# Sheet1.net
KiCad netlist of a schematic drawn in Altium Designer
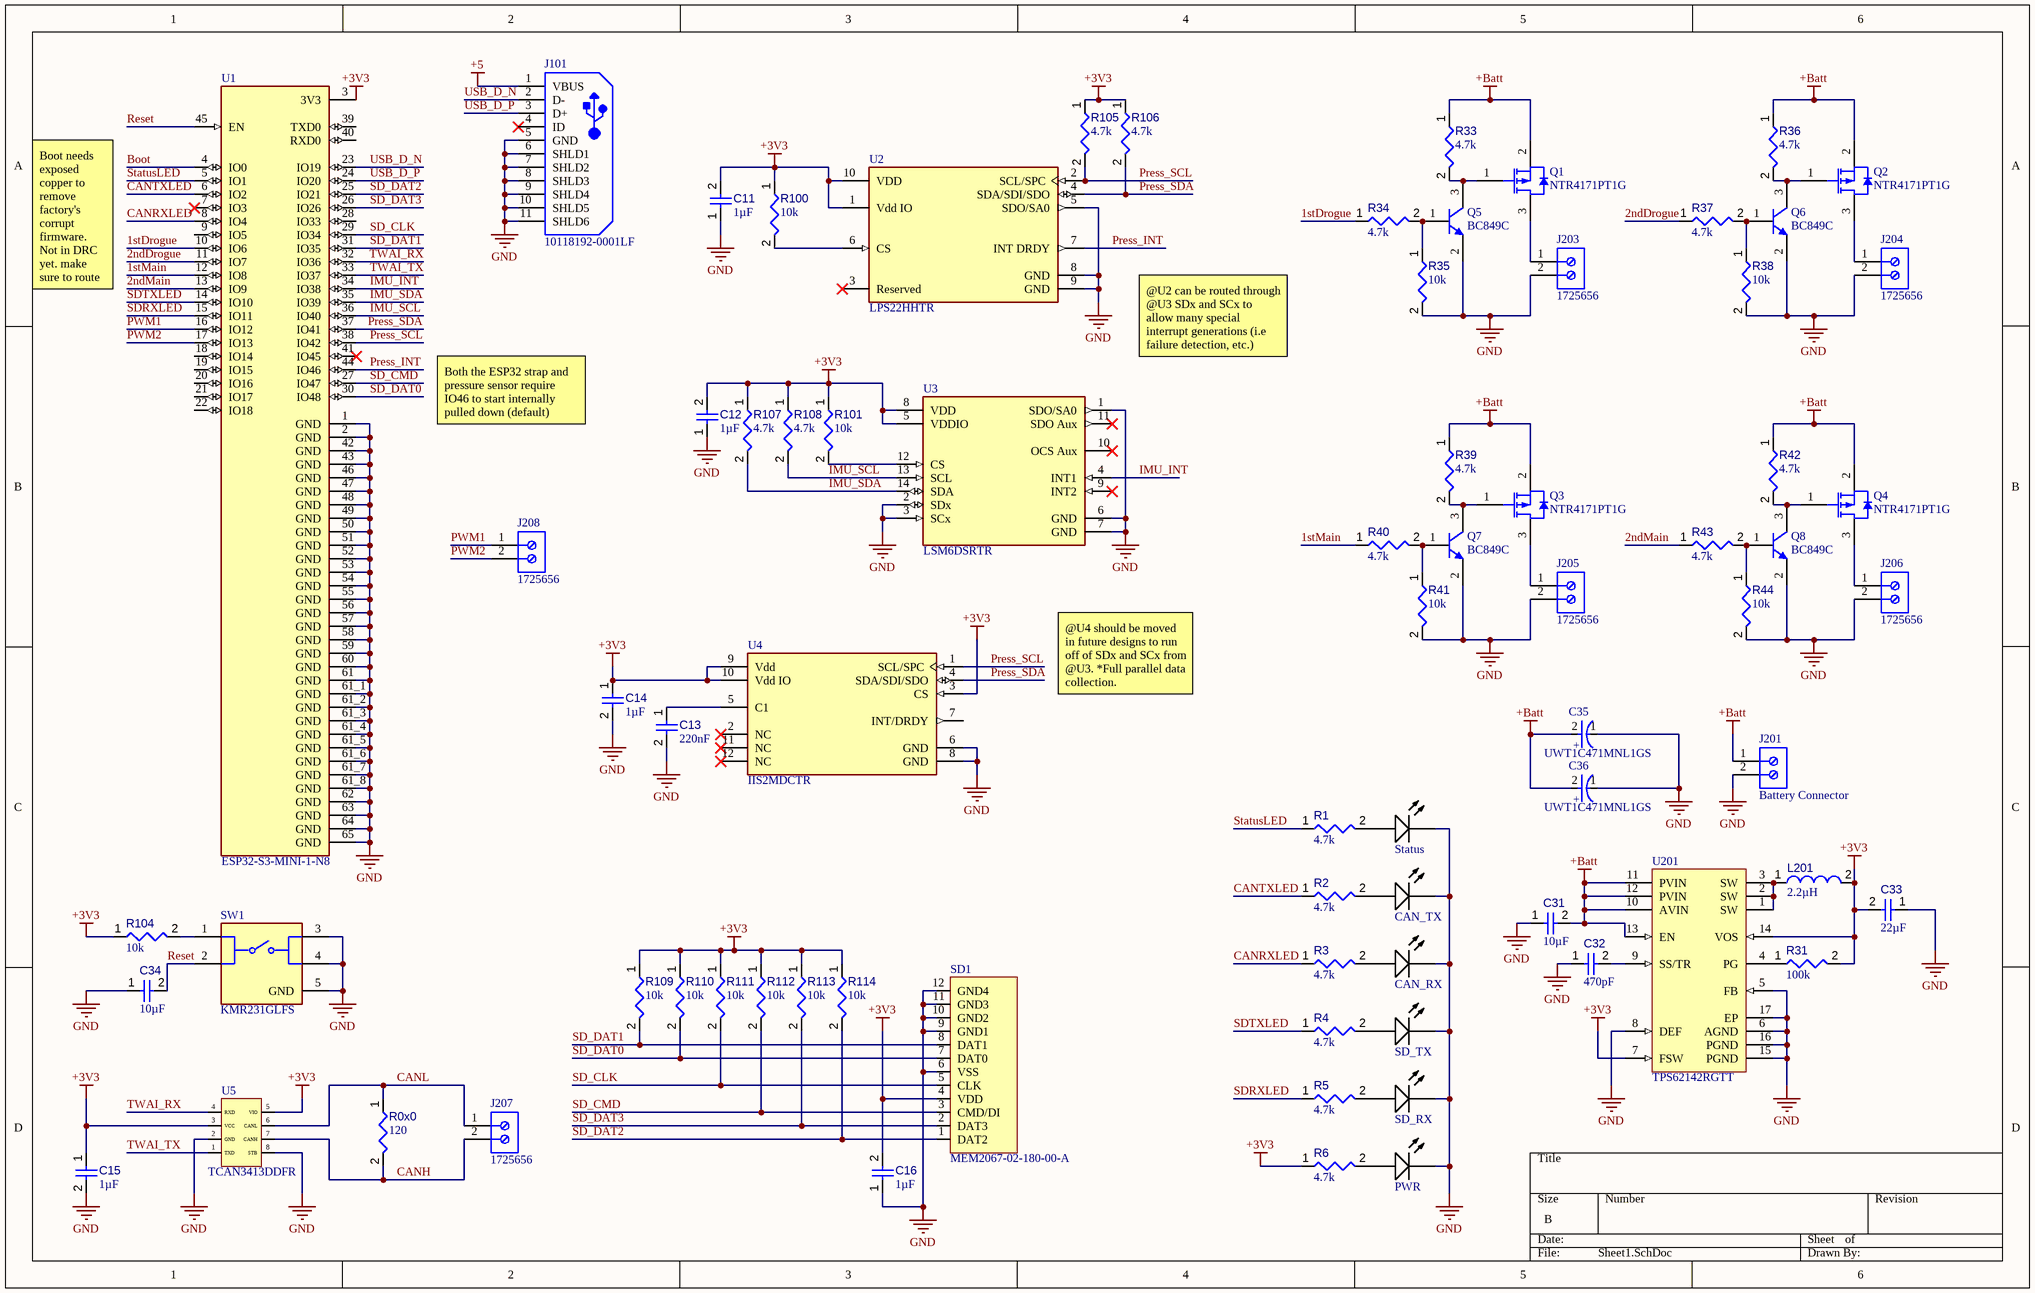
[diagram p0: Sheet1.SchDoc]

(export (version "E")
  (design (tool "Eeschema 10.0.6"))
  (components
    (comp (ref "C11")
      (value "1µF")
      (footprint "CAPC1005X55X25LL05T10")
      (description "Chip Capacitor, 1 uF, +/- 10%, 6.3 V, 0402 (1005 Metric)")
      (fields (field (name "TOLERANCE") "10%") (field (name "Comment") "Capacitor 1 uF +/- 10% 6.3 V 0402"))
      (libsource (lib "UTD") (part "CAP-NP-2"))
    )
    (comp (ref "C12")
      (value "1µF")
      (footprint "CAPC1005X55X25LL05T10")
      (description "Chip Capacitor, 1 uF, +/- 10%, 6.3 V, 0402 (1005 Metric)")
      (fields (field (name "TOLERANCE") "10%") (field (name "Comment") "Capacitor 1 uF +/- 10% 6.3 V 0402"))
      (libsource (lib "UTD") (part "CAP-NP-2"))
    )
    (comp (ref "C13")
      (value "220nF")
      (footprint "CAPC0402(1005)60_L")
      (description "Chip Capacitor, 220nF +/-20%, 10V, 0402, Thickness 0.6 mm")
      (fields (field (name "TOLERANCE") "10%") (field (name "Comment") "Capacitor 220nF +/-20% 10V 0402"))
      (libsource (lib "UTD") (part "CAP-NP-2"))
    )
    (comp (ref "C14")
      (value "1µF")
      (footprint "CAPC1005X55X25LL05T10")
      (description "Chip Capacitor, 1 uF, +/- 10%, 6.3 V, 0402 (1005 Metric)")
      (fields (field (name "TOLERANCE") "10%") (field (name "Comment") "Capacitor 1 uF +/- 10% 6.3 V 0402"))
      (libsource (lib "UTD") (part "CAP-NP-2"))
    )
    (comp (ref "C15")
      (value "1µF")
      (footprint "CAPC1005X55X25LL05T10")
      (description "Chip Capacitor, 1 uF, +/- 10%, 6.3 V, 0402 (1005 Metric)")
      (fields (field (name "TOLERANCE") "10%") (field (name "Comment") "Capacitor 1 uF +/- 10% 6.3 V 0402"))
      (libsource (lib "UTD") (part "CAP-NP-2"))
    )
    (comp (ref "C16")
      (value "1µF")
      (footprint "CAPC1005X55X25LL05T10")
      (description "Chip Capacitor, 1 uF, +/- 10%, 6.3 V, 0402 (1005 Metric)")
      (fields (field (name "TOLERANCE") "10%") (field (name "Comment") "Capacitor 1 uF +/- 10% 6.3 V 0402"))
      (libsource (lib "UTD") (part "CAP-NP-2"))
    )
    (comp (ref "C31")
      (value "10µF")
      (footprint "CAPC0603(1608)100_L")
      (description "Chip Capacitor, 10µF +/-20%, 10V, 0603, Thickness 1 mm")
      (fields (field (name "TOLERANCE") "10%") (field (name "Comment") "Capacitor 10µF +/-20% 10V 0603"))
      (libsource (lib "UTD") (part "CAP-NP-2"))
    )
    (comp (ref "C32")
      (value "470pF")
      (footprint "CAPC0603(1608)100_L")
      (description "Chip Capacitor, 470pF +/-20%, 10V, 0603, Thickness 1 mm")
      (fields (field (name "TOLERANCE") "10%") (field (name "Comment") "Capacitor 470pF +/-20% 50V 0402"))
      (libsource (lib "UTD") (part "CAP-NP-2"))
    )
    (comp (ref "C33")
      (value "22µF")
      (footprint "CAPC0603(1608)100_L")
      (description "Chip Capacitor, 10µF +/-20%, 10V, 0603, Thickness 1 mm")
      (fields (field (name "TOLERANCE") "10%") (field (name "Comment") "Capacitor 10µF +/-20% 10V 0603"))
      (libsource (lib "UTD") (part "CAP-NP-2"))
    )
    (comp (ref "C34")
      (value "10µF")
      (footprint "CAPC0603(1608)100_L")
      (description "Chip Capacitor, 10µF +/-20%, 10V, 0603, Thickness 1 mm")
      (fields (field (name "TOLERANCE") "10%") (field (name "Comment") "Capacitor 10µF +/-20% 10V 0603"))
      (libsource (lib "The University of Texas at Dallas") (part "CAP-NP-2"))
    )
    (comp (ref "C35")
      (value "UWT1C471MNL1GS")
      (footprint "FP-UWT1C471MNL1GS-MFG")
      (description "CAP ALUM 470UF 20% 16V SMD")
      (fields (field (name "VOLTAGE") "16V") (field (name "TOLERANCE") "20%"))
      (libsource (lib "Altium Content Vault") (part "203bc49f2ac43e59fd269a8c329ed05"))
    )
    (comp (ref "C36")
      (value "UWT1C471MNL1GS")
      (footprint "FP-UWT1C471MNL1GS-MFG")
      (description "CAP ALUM 470UF 20% 16V SMD")
      (fields (field (name "VOLTAGE") "16V") (field (name "TOLERANCE") "20%"))
      (libsource (lib "Altium Content Vault") (part "203bc49f2ac43e59fd269a8c329ed05"))
    )
    (comp (ref "CAN_RX")
      (value "HSMW-C191")
      (footprint "AVAG-HSMW-C191_V")
      (description "LED Uni-Color White, 78 mW, 20 mA, -40 to 85 degC, 2-Pin SMD, RoHS, Tape and Reel")
      (fields (field (name "POWER") "78mW") (field (name "MANUFACTURER") "Avago"))
      (libsource (lib "UTD") (part "LED-WHITE-AK-2"))
    )
    (comp (ref "CAN_TX")
      (value "HSMW-C191")
      (footprint "AVAG-HSMW-C191_V")
      (description "LED Uni-Color White, 78 mW, 20 mA, -40 to 85 degC, 2-Pin SMD, RoHS, Tape and Reel")
      (fields (field (name "POWER") "78mW") (field (name "MANUFACTURER") "Avago"))
      (libsource (lib "UTD") (part "LED-WHITE-AK-2"))
    )
    (comp (ref "J101")
      (value "10118192-0001LF")
      (footprint "FCI-10118192-0001LF-5_V")
      (description "Micro USB B Type Receptacle, -55 to 85 degC, 5-Pin SMD, RoHS, Tape and Reel")
      (fields (field (name "MANUFACTURER") "FCI"))
      (libsource (lib "Altium Content Vault") (part "USB-5-6SHLD"))
    )
    (comp (ref "J201")
      (value "Battery Connector")
      (footprint "PHOE-1725656-2")
      (description "Male Header, Pitch 2.54 mm, 1 x 2 Position, Height 9 mm, Tail Length 3.5 mm")
      (fields
        (field (name "MANUFACTURER PART NO.") "1725656")
        (field (name "MANUFACTURER") "Phoenix Contact")
      )
      (libsource (lib "Altium Content Vault") (part "CN-1P-F-TB2"))
    )
    (comp (ref "J203")
      (value "1725656")
      (footprint "PHOE-1725656-2")
      (description "Male Header, Pitch 2.54 mm, 1 x 2 Position, Height 9 mm, Tail Length 3.5 mm")
      (fields (field (name "MANUFACTURER") "Phoenix Contact"))
      (libsource (lib "Altium Content Vault") (part "CN-1P-F-TB2"))
    )
    (comp (ref "J204")
      (value "1725656")
      (footprint "PHOE-1725656-2")
      (description "Male Header, Pitch 2.54 mm, 1 x 2 Position, Height 9 mm, Tail Length 3.5 mm")
      (fields (field (name "MANUFACTURER") "Phoenix Contact"))
      (libsource (lib "Altium Content Vault") (part "CN-1P-F-TB2"))
    )
    (comp (ref "J205")
      (value "1725656")
      (footprint "PHOE-1725656-2")
      (description "Male Header, Pitch 2.54 mm, 1 x 2 Position, Height 9 mm, Tail Length 3.5 mm")
      (fields (field (name "MANUFACTURER") "Phoenix Contact"))
      (libsource (lib "Altium Content Vault") (part "CN-1P-F-TB2"))
    )
    (comp (ref "J206")
      (value "1725656")
      (footprint "PHOE-1725656-2")
      (description "Male Header, Pitch 2.54 mm, 1 x 2 Position, Height 9 mm, Tail Length 3.5 mm")
      (fields (field (name "MANUFACTURER") "Phoenix Contact"))
      (libsource (lib "Altium Content Vault") (part "CN-1P-F-TB2"))
    )
    (comp (ref "J207")
      (value "1725656")
      (footprint "PHOE-1725656-2")
      (description "Male Header, Pitch 2.54 mm, 1 x 2 Position, Height 9 mm, Tail Length 3.5 mm")
      (fields (field (name "MANUFACTURER") "Phoenix Contact"))
      (libsource (lib "Altium Content Vault") (part "CN-1P-F-TB2"))
    )
    (comp (ref "J208")
      (value "1725656")
      (footprint "PHOE-1725656-2")
      (description "Male Header, Pitch 2.54 mm, 1 x 2 Position, Height 9 mm, Tail Length 3.5 mm")
      (fields (field (name "MANUFACTURER") "Phoenix Contact"))
      (libsource (lib "Altium Content Vault") (part "CN-1P-F-TB2"))
    )
    (comp (ref "L201")
      (value "2.2µH")
      (footprint "INDC2520X100X60NL20T20")
      (description "Chip Inductor, 2.2 uH, +/- 20%, -55 to 125 degC, 1008 (2520 Metric), RoHS, Tape and Reel")
      (fields (field (name "TOLERANCE") "20%") (field (name "MANUFACTURER") "Murata"))
      (libsource (lib "UTD") (part "IND-2"))
    )
    (comp (ref "PWR")
      (value "HSMW-C191")
      (footprint "AVAG-HSMW-C191_V")
      (description "LED Uni-Color White, 78 mW, 20 mA, -40 to 85 degC, 2-Pin SMD, RoHS, Tape and Reel")
      (fields (field (name "POWER") "78mW") (field (name "MANUFACTURER") "Avago"))
      (libsource (lib "UTD") (part "LED-WHITE-AK-2"))
    )
    (comp (ref "Q1")
      (value "NTR4171PT1G")
      (footprint "ONSC-SOT-23-3-318-08_V")
      (description "Power MOSFET, -30 V, 3.5 A, Single P-Channel, 3-Pin SOT-23, Pb-Free, Tape and Reel")
      (fields (field (name "MANUFACTURER") "On Semiconductor"))
      (libsource (lib "Altium Content Vault") (part "ONSC-PMOS-G1S2D3-3_D"))
    )
    (comp (ref "Q2")
      (value "NTR4171PT1G")
      (footprint "ONSC-SOT-23-3-318-08_V")
      (description "Power MOSFET, -30 V, 3.5 A, Single P-Channel, 3-Pin SOT-23, Pb-Free, Tape and Reel")
      (fields (field (name "MANUFACTURER") "On Semiconductor"))
      (libsource (lib "Altium Content Vault") (part "ONSC-PMOS-G1S2D3-3_D"))
    )
    (comp (ref "Q3")
      (value "NTR4171PT1G")
      (footprint "ONSC-SOT-23-3-318-08_V")
      (description "Power MOSFET, -30 V, 3.5 A, Single P-Channel, 3-Pin SOT-23, Pb-Free, Tape and Reel")
      (fields (field (name "MANUFACTURER") "On Semiconductor"))
      (libsource (lib "Altium Content Vault") (part "ONSC-PMOS-G1S2D3-3_D"))
    )
    (comp (ref "Q4")
      (value "NTR4171PT1G")
      (footprint "ONSC-SOT-23-3-318-08_V")
      (description "Power MOSFET, -30 V, 3.5 A, Single P-Channel, 3-Pin SOT-23, Pb-Free, Tape and Reel")
      (fields (field (name "MANUFACTURER") "On Semiconductor"))
      (libsource (lib "Altium Content Vault") (part "ONSC-PMOS-G1S2D3-3_D"))
    )
    (comp (ref "Q5")
      (value "BC849C")
      (footprint "INF-SOT23_L")
      (description "NPN Silicon AF Transistor, 30 V VCEO, 100 mA IC, SOT23, Reel, Green")
      (fields (field (name "MANUFACTURER") "Infineon"))
      (libsource (lib "Altium Content Vault") (part "INF-BJTNPN-BEC-3"))
    )
    (comp (ref "Q6")
      (value "BC849C")
      (footprint "INF-SOT23_L")
      (description "NPN Silicon AF Transistor, 30 V VCEO, 100 mA IC, SOT23, Reel, Green")
      (fields (field (name "MANUFACTURER") "Infineon"))
      (libsource (lib "Altium Content Vault") (part "INF-BJTNPN-BEC-3"))
    )
    (comp (ref "Q7")
      (value "BC849C")
      (footprint "INF-SOT23_L")
      (description "NPN Silicon AF Transistor, 30 V VCEO, 100 mA IC, SOT23, Reel, Green")
      (fields (field (name "MANUFACTURER") "Infineon"))
      (libsource (lib "Altium Content Vault") (part "INF-BJTNPN-BEC-3"))
    )
    (comp (ref "Q8")
      (value "BC849C")
      (footprint "INF-SOT23_L")
      (description "NPN Silicon AF Transistor, 30 V VCEO, 100 mA IC, SOT23, Reel, Green")
      (fields (field (name "MANUFACTURER") "Infineon"))
      (libsource (lib "Altium Content Vault") (part "INF-BJTNPN-BEC-3"))
    )
    (comp (ref "R0x0")
      (value "120")
      (footprint "RESC0603(1608)_L")
      (description "Chip Resistor, 120 Ohms, +/-5 %, 0.1 W, -55 to 155 degC, 0603")
      (fields (field (name "POWER") "100mW") (field (name "TOLERANCE") "5%"))
      (libsource (lib "The University of Texas at Dallas") (part "RES-2"))
    )
    (comp (ref "R1")
      (value "4.7k")
      (footprint "RESC1005X40X25ML05T05")
      (description "Chip Resistor, 4.7 KOhm, +/- 1%, 63 mW, -55 to 155 degC, 0402 (1005 Metric)")
      (fields (field (name "TOLERANCE") "1%") (field (name "POWER") "63mW"))
      (libsource (lib "UTD") (part "RES-2"))
    )
    (comp (ref "R2")
      (value "4.7k")
      (footprint "RESC1005X40X25ML05T05")
      (description "Chip Resistor, 4.7 KOhm, +/- 1%, 63 mW, -55 to 155 degC, 0402 (1005 Metric)")
      (fields (field (name "TOLERANCE") "1%") (field (name "POWER") "63mW"))
      (libsource (lib "UTD") (part "RES-2"))
    )
    (comp (ref "R3")
      (value "4.7k")
      (footprint "RESC1005X40X25ML05T05")
      (description "Chip Resistor, 4.7 KOhm, +/- 1%, 63 mW, -55 to 155 degC, 0402 (1005 Metric)")
      (fields (field (name "TOLERANCE") "1%") (field (name "POWER") "63mW"))
      (libsource (lib "UTD") (part "RES-2"))
    )
    (comp (ref "R4")
      (value "4.7k")
      (footprint "RESC1005X40X25ML05T05")
      (description "Chip Resistor, 4.7 KOhm, +/- 1%, 63 mW, -55 to 155 degC, 0402 (1005 Metric)")
      (fields (field (name "TOLERANCE") "1%") (field (name "POWER") "63mW"))
      (libsource (lib "UTD") (part "RES-2"))
    )
    (comp (ref "R5")
      (value "4.7k")
      (footprint "RESC1005X40X25ML05T05")
      (description "Chip Resistor, 4.7 KOhm, +/- 1%, 63 mW, -55 to 155 degC, 0402 (1005 Metric)")
      (fields (field (name "TOLERANCE") "1%") (field (name "POWER") "63mW"))
      (libsource (lib "UTD") (part "RES-2"))
    )
    (comp (ref "R6")
      (value "4.7k")
      (footprint "RESC1005X40X25ML05T05")
      (description "Chip Resistor, 4.7 KOhm, +/- 1%, 63 mW, -55 to 155 degC, 0402 (1005 Metric)")
      (fields (field (name "TOLERANCE") "1%") (field (name "POWER") "63mW"))
      (libsource (lib "UTD") (part "RES-2"))
    )
    (comp (ref "R31")
      (value "100k")
      (footprint "RESC0402(1005)_L")
      (description "Chip Resistor, 100 kOhms, +/-1 %, 63 mW, -55 to 155 degC, 0402")
      (fields (field (name "TOLERANCE") "1%") (field (name "POWER") "63mW"))
      (libsource (lib "UTD") (part "RES-2"))
    )
    (comp (ref "R33")
      (value "4.7k")
      (footprint "RESC1005X40X25ML05T05")
      (description "Chip Resistor, 4.7 KOhm, +/- 1%, 63 mW, -55 to 155 degC, 0402 (1005 Metric)")
      (fields (field (name "TOLERANCE") "1%") (field (name "POWER") "63mW"))
      (libsource (lib "UTD") (part "RES-2"))
    )
    (comp (ref "R34")
      (value "4.7k")
      (footprint "RESC1005X40X25ML05T05")
      (description "Chip Resistor, 4.7 KOhm, +/- 1%, 63 mW, -55 to 155 degC, 0402 (1005 Metric)")
      (fields (field (name "TOLERANCE") "1%") (field (name "POWER") "63mW"))
      (libsource (lib "UTD") (part "RES-2"))
    )
    (comp (ref "R35")
      (value "10k")
      (footprint "RESC1005X40X25ML05T05")
      (description "Chip Resistor, 10 KOhm, +/- 1%, 63 mW, -55 to 155 degC, 0402 (1005 Metric)")
      (fields (field (name "POWER") "63mW") (field (name "TOLERANCE") "1%"))
      (libsource (lib "UTD") (part "RES-2"))
    )
    (comp (ref "R36")
      (value "4.7k")
      (footprint "RESC1005X40X25ML05T05")
      (description "Chip Resistor, 4.7 KOhm, +/- 1%, 63 mW, -55 to 155 degC, 0402 (1005 Metric)")
      (fields (field (name "TOLERANCE") "1%") (field (name "POWER") "63mW"))
      (libsource (lib "UTD") (part "RES-2"))
    )
    (comp (ref "R37")
      (value "4.7k")
      (footprint "RESC1005X40X25ML05T05")
      (description "Chip Resistor, 4.7 KOhm, +/- 1%, 63 mW, -55 to 155 degC, 0402 (1005 Metric)")
      (fields (field (name "TOLERANCE") "1%") (field (name "POWER") "63mW"))
      (libsource (lib "UTD") (part "RES-2"))
    )
    (comp (ref "R38")
      (value "10k")
      (footprint "RESC1005X40X25ML05T05")
      (description "Chip Resistor, 10 KOhm, +/- 1%, 63 mW, -55 to 155 degC, 0402 (1005 Metric)")
      (fields (field (name "POWER") "63mW") (field (name "TOLERANCE") "1%"))
      (libsource (lib "UTD") (part "RES-2"))
    )
    (comp (ref "R39")
      (value "4.7k")
      (footprint "RESC1005X40X25ML05T05")
      (description "Chip Resistor, 4.7 KOhm, +/- 1%, 63 mW, -55 to 155 degC, 0402 (1005 Metric)")
      (fields (field (name "TOLERANCE") "1%") (field (name "POWER") "63mW"))
      (libsource (lib "UTD") (part "RES-2"))
    )
    (comp (ref "R40")
      (value "4.7k")
      (footprint "RESC1005X40X25ML05T05")
      (description "Chip Resistor, 4.7 KOhm, +/- 1%, 63 mW, -55 to 155 degC, 0402 (1005 Metric)")
      (fields (field (name "TOLERANCE") "1%") (field (name "POWER") "63mW"))
      (libsource (lib "UTD") (part "RES-2"))
    )
    (comp (ref "R41")
      (value "10k")
      (footprint "RESC1005X40X25ML05T05")
      (description "Chip Resistor, 10 KOhm, +/- 1%, 63 mW, -55 to 155 degC, 0402 (1005 Metric)")
      (fields (field (name "POWER") "63mW") (field (name "TOLERANCE") "1%"))
      (libsource (lib "UTD") (part "RES-2"))
    )
    (comp (ref "R42")
      (value "4.7k")
      (footprint "RESC1005X40X25ML05T05")
      (description "Chip Resistor, 4.7 KOhm, +/- 1%, 63 mW, -55 to 155 degC, 0402 (1005 Metric)")
      (fields (field (name "TOLERANCE") "1%") (field (name "POWER") "63mW"))
      (libsource (lib "UTD") (part "RES-2"))
    )
    (comp (ref "R43")
      (value "4.7k")
      (footprint "RESC1005X40X25ML05T05")
      (description "Chip Resistor, 4.7 KOhm, +/- 1%, 63 mW, -55 to 155 degC, 0402 (1005 Metric)")
      (fields (field (name "TOLERANCE") "1%") (field (name "POWER") "63mW"))
      (libsource (lib "UTD") (part "RES-2"))
    )
    (comp (ref "R44")
      (value "10k")
      (footprint "RESC1005X40X25ML05T05")
      (description "Chip Resistor, 10 KOhm, +/- 1%, 63 mW, -55 to 155 degC, 0402 (1005 Metric)")
      (fields (field (name "POWER") "63mW") (field (name "TOLERANCE") "1%"))
      (libsource (lib "UTD") (part "RES-2"))
    )
    (comp (ref "R100")
      (value "10k")
      (footprint "RESC1005X40X25ML05T05")
      (description "Chip Resistor, 10 KOhm, +/- 1%, 63 mW, -55 to 155 degC, 0402 (1005 Metric)")
      (fields (field (name "POWER") "63mW") (field (name "TOLERANCE") "1%"))
      (libsource (lib "UTD") (part "RES-2"))
    )
    (comp (ref "R101")
      (value "10k")
      (footprint "RESC1005X40X25ML05T05")
      (description "Chip Resistor, 10 KOhm, +/- 1%, 63 mW, -55 to 155 degC, 0402 (1005 Metric)")
      (fields (field (name "POWER") "63mW") (field (name "TOLERANCE") "1%"))
      (libsource (lib "UTD") (part "RES-2"))
    )
    (comp (ref "R104")
      (value "10k")
      (footprint "RESC1005X40X25ML05T05")
      (description "Chip Resistor, 10 KOhm, +/- 1%, 63 mW, -55 to 155 degC, 0402 (1005 Metric)")
      (fields (field (name "POWER") "63mW") (field (name "TOLERANCE") "1%"))
      (libsource (lib "UTD") (part "RES-2"))
    )
    (comp (ref "R105")
      (value "4.7k")
      (footprint "RESC1005X40X25ML05T05")
      (description "Chip Resistor, 4.7 KOhm, +/- 1%, 63 mW, -55 to 155 degC, 0402 (1005 Metric)")
      (fields (field (name "TOLERANCE") "1%") (field (name "POWER") "63mW"))
      (libsource (lib "UTD") (part "RES-2"))
    )
    (comp (ref "R106")
      (value "4.7k")
      (footprint "RESC1005X40X25ML05T05")
      (description "Chip Resistor, 4.7 KOhm, +/- 1%, 63 mW, -55 to 155 degC, 0402 (1005 Metric)")
      (fields (field (name "TOLERANCE") "1%") (field (name "POWER") "63mW"))
      (libsource (lib "UTD") (part "RES-2"))
    )
    (comp (ref "R107")
      (value "4.7k")
      (footprint "RESC1005X40X25ML05T05")
      (description "Chip Resistor, 4.7 KOhm, +/- 1%, 63 mW, -55 to 155 degC, 0402 (1005 Metric)")
      (fields (field (name "TOLERANCE") "1%") (field (name "POWER") "63mW"))
      (libsource (lib "UTD") (part "RES-2"))
    )
    (comp (ref "R108")
      (value "4.7k")
      (footprint "RESC1005X40X25ML05T05")
      (description "Chip Resistor, 4.7 KOhm, +/- 1%, 63 mW, -55 to 155 degC, 0402 (1005 Metric)")
      (fields (field (name "TOLERANCE") "1%") (field (name "POWER") "63mW"))
      (libsource (lib "UTD") (part "RES-2"))
    )
    (comp (ref "R109")
      (value "10k")
      (footprint "RESC1005X40X25ML05T05")
      (description "Chip Resistor, 10 KOhm, +/- 1%, 63 mW, -55 to 155 degC, 0402 (1005 Metric)")
      (fields (field (name "POWER") "63mW") (field (name "TOLERANCE") "1%"))
      (libsource (lib "UTD") (part "RES-2"))
    )
    (comp (ref "R110")
      (value "10k")
      (footprint "RESC1005X40X25ML05T05")
      (description "Chip Resistor, 10 KOhm, +/- 1%, 63 mW, -55 to 155 degC, 0402 (1005 Metric)")
      (fields (field (name "POWER") "63mW") (field (name "TOLERANCE") "1%"))
      (libsource (lib "UTD") (part "RES-2"))
    )
    (comp (ref "R111")
      (value "10k")
      (footprint "RESC1005X40X25ML05T05")
      (description "Chip Resistor, 10 KOhm, +/- 1%, 63 mW, -55 to 155 degC, 0402 (1005 Metric)")
      (fields (field (name "POWER") "63mW") (field (name "TOLERANCE") "1%"))
      (libsource (lib "UTD") (part "RES-2"))
    )
    (comp (ref "R112")
      (value "10k")
      (footprint "RESC1005X40X25ML05T05")
      (description "Chip Resistor, 10 KOhm, +/- 1%, 63 mW, -55 to 155 degC, 0402 (1005 Metric)")
      (fields (field (name "POWER") "63mW") (field (name "TOLERANCE") "1%"))
      (libsource (lib "UTD") (part "RES-2"))
    )
    (comp (ref "R113")
      (value "10k")
      (footprint "RESC1005X40X25ML05T05")
      (description "Chip Resistor, 10 KOhm, +/- 1%, 63 mW, -55 to 155 degC, 0402 (1005 Metric)")
      (fields (field (name "POWER") "63mW") (field (name "TOLERANCE") "1%"))
      (libsource (lib "UTD") (part "RES-2"))
    )
    (comp (ref "R114")
      (value "10k")
      (footprint "RESC1005X40X25ML05T05")
      (description "Chip Resistor, 10 KOhm, +/- 1%, 63 mW, -55 to 155 degC, 0402 (1005 Metric)")
      (fields (field (name "POWER") "63mW") (field (name "TOLERANCE") "1%"))
      (libsource (lib "UTD") (part "RES-2"))
    )
    (comp (ref "SD1")
      (value "MEM2067-02-180-00-A")
      (footprint "MEM2067-02-180-00-A_REVB")
      (description "MICRO SD HINGED, SMT, 1.80MM PRO")
      (fields (field (name "MANUFACTURER") "Global Connector Technology"))
      (libsource (lib "UTD") (part "MEM2067-02-180-00-A"))
    )
    (comp (ref "SD_RX")
      (value "HSMW-C191")
      (footprint "AVAG-HSMW-C191_V")
      (description "LED Uni-Color White, 78 mW, 20 mA, -40 to 85 degC, 2-Pin SMD, RoHS, Tape and Reel")
      (fields (field (name "POWER") "78mW") (field (name "MANUFACTURER") "Avago"))
      (libsource (lib "UTD") (part "LED-WHITE-AK-2"))
    )
    (comp (ref "SD_TX")
      (value "HSMW-C191")
      (footprint "AVAG-HSMW-C191_V")
      (description "LED Uni-Color White, 78 mW, 20 mA, -40 to 85 degC, 2-Pin SMD, RoHS, Tape and Reel")
      (fields (field (name "POWER") "78mW") (field (name "MANUFACTURER") "Avago"))
      (libsource (lib "UTD") (part "LED-WHITE-AK-2"))
    )
    (comp (ref "Status")
      (value "HSMW-C191")
      (footprint "AVAG-HSMW-C191_V")
      (description "LED Uni-Color White, 78 mW, 20 mA, -40 to 85 degC, 2-Pin SMD, RoHS, Tape and Reel")
      (fields (field (name "POWER") "78mW") (field (name "MANUFACTURER") "Avago"))
      (libsource (lib "UTD") (part "LED-WHITE-AK-2"))
    )
    (comp (ref "SW1")
      (value "KMR231GLFS")
      (footprint "FP-KMR231GLFS-MFG")
      (description "SWITCH TACTILE SPST-NO 0.05A 32V")
      (libsource (lib "Altium Content Vault") (part "4ba73034ab40b7b0ce053ff7ec1e5b4"))
    )
    (comp (ref "U1")
      (value "ESP32-S3-MINI-1-N8")
      (footprint "XCVR_ESP32-S3-MINI-1-N8")
      (fields (field (name "MF") "{'manufacturer': u'Espressif Systems'}"))
      (libsource (lib "UTD") (part "ESP32-S3-MINI-1-N8"))
    )
    (comp (ref "U2")
      (value "LPS22HHTR")
      (footprint "FP-HLGA-10L-DM00386636-MFG")
      (description "CONSUMER MEMS")
      (fields
        (field (name "OCTOPART") "https://octopart.com/lps22hhtr-stmicroelectronics-94834025")
        (field (name "MANUFACTURER") "STMicroelectronics")
      )
      (libsource (lib "Altium Content Vault") (part "af158f922cca5ffd55045a3797efeaf"))
    )
    (comp (ref "U3")
      (value "LSM6DSRTR")
      (footprint "FP-LGA-14L-DM00249496-MFG")
      (description "INEMO INERTIAL MODULE: 3D ACCELE")
      (fields
        (field (name "MANUFACTURER") "STMicroelectronics")
        (field (name "OCTOPART") "https://octopart.com/lsm6dsrtr-stmicroelectronics-93180177")
      )
      (libsource (lib "Altium Content Vault") (part "274f04aa0157ef83b57917dd63188b9"))
    )
    (comp (ref "U4")
      (value "IIS2MDCTR")
      (footprint "FP-LGA-12-DM00170568-MFG")
      (description "SENSOR MR I2C/SPI 12LGA")
      (libsource (lib "Altium Content Vault") (part "9127e88978c08266a31c65258fd487e"))
    )
    (comp (ref "U5")
      (value "TCAN3413DDFR")
      (footprint "TSOP65P280X110-8N")
      (description "3.3-V CAN FD transceiver with flexible IO and standby mode 8-SOT-23-THIN -40 to 125")
      (libsource (lib "The University of Texas at Dallas") (part "TCAN3413DDFR-Symbol-1"))
    )
    (comp (ref "U201")
      (value "TPS62142RGTT")
      (footprint "RGT0016C_V")
      (fields (field (name "MANUFACTURER") "Texas Instruments"))
      (libsource (lib "Altium Content Vault") (part "TI-TPS62142RGT16-1700X1700TP"))
    )
  )
  (nets
    (net (code "1") (name "+3V3") (class "Default")
      (node (ref "C11") (pin "2") (pinfunction "2_2") (pintype "passive"))
      (node (ref "C12") (pin "2") (pinfunction "2_2") (pintype "passive"))
      (node (ref "C14") (pin "1") (pinfunction "1_1") (pintype "passive"))
      (node (ref "C15") (pin "1") (pinfunction "1_1") (pintype "passive"))
      (node (ref "C16") (pin "2") (pinfunction "2_2") (pintype "passive"))
      (node (ref "C33") (pin "2") (pinfunction "2_2") (pintype "passive"))
      (node (ref "L201") (pin "2") (pinfunction "2_2") (pintype "passive"))
      (node (ref "R100") (pin "1") (pinfunction "1_1") (pintype "passive"))
      (node (ref "R101") (pin "1") (pinfunction "1_1") (pintype "passive"))
      (node (ref "R104") (pin "1") (pinfunction "1_1") (pintype "passive"))
      (node (ref "R105") (pin "1") (pinfunction "1_1") (pintype "passive"))
      (node (ref "R106") (pin "1") (pinfunction "1_1") (pintype "passive"))
      (node (ref "R107") (pin "1") (pinfunction "1_1") (pintype "passive"))
      (node (ref "R108") (pin "1") (pinfunction "1_1") (pintype "passive"))
      (node (ref "R109") (pin "1") (pinfunction "1_1") (pintype "passive"))
      (node (ref "R110") (pin "1") (pinfunction "1_1") (pintype "passive"))
      (node (ref "R111") (pin "1") (pinfunction "1_1") (pintype "passive"))
      (node (ref "R112") (pin "1") (pinfunction "1_1") (pintype "passive"))
      (node (ref "R113") (pin "1") (pinfunction "1_1") (pintype "passive"))
      (node (ref "R114") (pin "1") (pinfunction "1_1") (pintype "passive"))
      (node (ref "R31") (pin "2") (pinfunction "2_2") (pintype "passive"))
      (node (ref "R6") (pin "1") (pinfunction "1_1") (pintype "passive"))
      (node (ref "SD1") (pin "4") (pinfunction "VDD_4") (pintype "passive"))
      (node (ref "U1") (pin "3") (pinfunction "3V3_3") (pintype "power_in"))
      (node (ref "U2") (pin "1") (pinfunction "Vdd_IO_1") (pintype "power_in"))
      (node (ref "U2") (pin "10") (pinfunction "VDD_10") (pintype "power_in"))
      (node (ref "U201") (pin "14") (pinfunction "VOS_14") (pintype "input"))
      (node (ref "U201") (pin "7") (pinfunction "FSW_7") (pintype "input"))
      (node (ref "U3") (pin "5") (pinfunction "VDDIO_5") (pintype "power_in"))
      (node (ref "U3") (pin "8") (pinfunction "VDD_8") (pintype "power_in"))
      (node (ref "U4") (pin "10") (pinfunction "Vdd_IO_10") (pintype "power_in"))
      (node (ref "U4") (pin "3") (pinfunction "CS_3") (pintype "input"))
      (node (ref "U4") (pin "9") (pinfunction "Vdd_9") (pintype "power_in"))
      (node (ref "U5") (pin "3") (pinfunction "VCC_3") (pintype "passive"))
      (node (ref "U5") (pin "5") (pinfunction "VIO_5") (pintype "passive"))
    )
    (net (code "2") (name "+5") (class "Default")
      (node (ref "J101") (pin "1") (pinfunction "VBUS_1") (pintype "passive"))
    )
    (net (code "3") (name "+Batt") (class "Default")
      (node (ref "C31") (pin "2") (pinfunction "2_2") (pintype "passive"))
      (node (ref "C35") (pin "2") (pinfunction "A_2") (pintype "passive"))
      (node (ref "C36") (pin "2") (pinfunction "A_2") (pintype "passive"))
      (node (ref "J201") (pin "1") (pinfunction "1_1") (pintype "passive"))
      (node (ref "Q1") (pin "2") (pinfunction "S_2") (pintype "passive"))
      (node (ref "Q2") (pin "2") (pinfunction "S_2") (pintype "passive"))
      (node (ref "Q3") (pin "2") (pinfunction "S_2") (pintype "passive"))
      (node (ref "Q4") (pin "2") (pinfunction "S_2") (pintype "passive"))
      (node (ref "R33") (pin "1") (pinfunction "1_1") (pintype "passive"))
      (node (ref "R36") (pin "1") (pinfunction "1_1") (pintype "passive"))
      (node (ref "R39") (pin "1") (pinfunction "1_1") (pintype "passive"))
      (node (ref "R42") (pin "1") (pinfunction "1_1") (pintype "passive"))
      (node (ref "U201") (pin "10") (pinfunction "AVIN_10") (pintype "power_in"))
      (node (ref "U201") (pin "11") (pinfunction "PVIN_11") (pintype "power_in"))
      (node (ref "U201") (pin "12") (pinfunction "PVIN_12") (pintype "power_in"))
      (node (ref "U201") (pin "13") (pinfunction "EN_13") (pintype "input"))
    )
    (net (code "4") (name "/1stDrogue") (class "Default")
      (node (ref "R34") (pin "1") (pinfunction "1_1") (pintype "passive"))
      (node (ref "U1") (pin "10") (pinfunction "IO6_10") (pintype "bidirectional"))
    )
    (net (code "5") (name "/1stMain") (class "Default")
      (node (ref "R40") (pin "1") (pinfunction "1_1") (pintype "passive"))
      (node (ref "U1") (pin "12") (pinfunction "IO8_12") (pintype "bidirectional"))
    )
    (net (code "6") (name "/2ndDrogue") (class "Default")
      (node (ref "R37") (pin "1") (pinfunction "1_1") (pintype "passive"))
      (node (ref "U1") (pin "11") (pinfunction "IO7_11") (pintype "bidirectional"))
    )
    (net (code "7") (name "/2ndMain") (class "Default")
      (node (ref "R43") (pin "1") (pinfunction "1_1") (pintype "passive"))
      (node (ref "U1") (pin "13") (pinfunction "IO9_13") (pintype "bidirectional"))
    )
    (net (code "8") (name "/Boot") (class "Default")
      (node (ref "U1") (pin "4") (pinfunction "IO0_4") (pintype "bidirectional"))
    )
    (net (code "9") (name "/CANH") (class "Default")
      (node (ref "J207") (pin "2") (pinfunction "2_2") (pintype "passive"))
      (node (ref "R0x0") (pin "2") (pinfunction "2_2") (pintype "passive"))
      (node (ref "U5") (pin "7") (pinfunction "CANH_7") (pintype "passive"))
    )
    (net (code "10") (name "/CANL") (class "Default")
      (node (ref "J207") (pin "1") (pinfunction "1_1") (pintype "passive"))
      (node (ref "R0x0") (pin "1") (pinfunction "1_1") (pintype "passive"))
      (node (ref "U5") (pin "6") (pinfunction "CANL_6") (pintype "passive"))
    )
    (net (code "11") (name "/CANRXLED") (class "Default")
      (node (ref "R3") (pin "1") (pinfunction "1_1") (pintype "passive"))
      (node (ref "U1") (pin "8") (pinfunction "IO4_8") (pintype "bidirectional"))
    )
    (net (code "12") (name "/CANTXLED") (class "Default")
      (node (ref "R2") (pin "1") (pinfunction "1_1") (pintype "passive"))
      (node (ref "U1") (pin "6") (pinfunction "IO2_6") (pintype "bidirectional"))
    )
    (net (code "13") (name "/IMU_INT") (class "Default")
      (node (ref "U1") (pin "34") (pinfunction "IO38_34") (pintype "bidirectional"))
      (node (ref "U3") (pin "4") (pinfunction "INT1_4") (pintype "input"))
    )
    (net (code "14") (name "/IMU_SCL") (class "Default")
      (node (ref "R108") (pin "2") (pinfunction "2_2") (pintype "passive"))
      (node (ref "U1") (pin "36") (pinfunction "IO40_36") (pintype "bidirectional"))
      (node (ref "U3") (pin "13") (pinfunction "SCL_13") (pintype "input"))
    )
    (net (code "15") (name "/IMU_SDA") (class "Default")
      (node (ref "R107") (pin "2") (pinfunction "2_2") (pintype "passive"))
      (node (ref "U1") (pin "35") (pinfunction "IO39_35") (pintype "bidirectional"))
      (node (ref "U3") (pin "14") (pinfunction "SDA_14") (pintype "bidirectional"))
    )
    (net (code "16") (name "/PWM1") (class "Default")
      (node (ref "J208") (pin "1") (pinfunction "1_1") (pintype "passive"))
      (node (ref "U1") (pin "16") (pinfunction "IO12_16") (pintype "bidirectional"))
    )
    (net (code "17") (name "/PWM2") (class "Default")
      (node (ref "J208") (pin "2") (pinfunction "2_2") (pintype "passive"))
      (node (ref "U1") (pin "17") (pinfunction "IO13_17") (pintype "bidirectional"))
    )
    (net (code "18") (name "/Press_INT") (class "Default")
      (node (ref "U1") (pin "44") (pinfunction "IO46_44") (pintype "bidirectional"))
      (node (ref "U2") (pin "7") (pinfunction "INT_DRDY_7") (pintype "output"))
    )
    (net (code "19") (name "/Press_SCL") (class "Default")
      (node (ref "R105") (pin "2") (pinfunction "2_2") (pintype "passive"))
      (node (ref "U1") (pin "38") (pinfunction "IO42_38") (pintype "bidirectional"))
      (node (ref "U2") (pin "2") (pinfunction "SCL/SPC_2") (pintype "input"))
      (node (ref "U4") (pin "1") (pinfunction "SCL/SPC_1") (pintype "input"))
    )
    (net (code "20") (name "/Press_SDA") (class "Default")
      (node (ref "R106") (pin "2") (pinfunction "2_2") (pintype "passive"))
      (node (ref "U1") (pin "37") (pinfunction "IO41_37") (pintype "bidirectional"))
      (node (ref "U2") (pin "4") (pinfunction "SDA/SDI/SDO_4") (pintype "bidirectional"))
      (node (ref "U4") (pin "4") (pinfunction "SDA/SDI/SDO_4") (pintype "bidirectional"))
    )
    (net (code "21") (name "/Reset") (class "Default")
      (node (ref "C34") (pin "2") (pinfunction "2_2") (pintype "passive"))
      (node (ref "SW1") (pin "2") (pinfunction "2_2") (pintype "passive"))
      (node (ref "U1") (pin "45") (pinfunction "EN_45") (pintype "input"))
    )
    (net (code "22") (name "/SDRXLED") (class "Default")
      (node (ref "R5") (pin "1") (pinfunction "1_1") (pintype "passive"))
      (node (ref "U1") (pin "15") (pinfunction "IO11_15") (pintype "bidirectional"))
    )
    (net (code "23") (name "/SDTXLED") (class "Default")
      (node (ref "R4") (pin "1") (pinfunction "1_1") (pintype "passive"))
      (node (ref "U1") (pin "14") (pinfunction "IO10_14") (pintype "bidirectional"))
    )
    (net (code "24") (name "/SD_CLK") (class "Default")
      (node (ref "R111") (pin "2") (pinfunction "2_2") (pintype "passive"))
      (node (ref "SD1") (pin "5") (pinfunction "CLK_5") (pintype "passive"))
      (node (ref "U1") (pin "29") (pinfunction "IO34_29") (pintype "bidirectional"))
    )
    (net (code "25") (name "/SD_CMD") (class "Default")
      (node (ref "R112") (pin "2") (pinfunction "2_2") (pintype "passive"))
      (node (ref "SD1") (pin "3") (pinfunction "CMD/DI_3") (pintype "passive"))
      (node (ref "U1") (pin "27") (pinfunction "IO47_27") (pintype "bidirectional"))
    )
    (net (code "26") (name "/SD_DAT0") (class "Default")
      (node (ref "R110") (pin "2") (pinfunction "2_2") (pintype "passive"))
      (node (ref "SD1") (pin "7") (pinfunction "DAT0_7") (pintype "passive"))
      (node (ref "U1") (pin "30") (pinfunction "IO48_30") (pintype "bidirectional"))
    )
    (net (code "27") (name "/SD_DAT1") (class "Default")
      (node (ref "R109") (pin "2") (pinfunction "2_2") (pintype "passive"))
      (node (ref "SD1") (pin "8") (pinfunction "DAT1_8") (pintype "passive"))
      (node (ref "U1") (pin "31") (pinfunction "IO35_31") (pintype "bidirectional"))
    )
    (net (code "28") (name "/SD_DAT2") (class "Default")
      (node (ref "R114") (pin "2") (pinfunction "2_2") (pintype "passive"))
      (node (ref "SD1") (pin "1") (pinfunction "DAT2_1") (pintype "passive"))
      (node (ref "U1") (pin "25") (pinfunction "IO21_25") (pintype "bidirectional"))
    )
    (net (code "29") (name "/SD_DAT3") (class "Default")
      (node (ref "R113") (pin "2") (pinfunction "2_2") (pintype "passive"))
      (node (ref "SD1") (pin "2") (pinfunction "DAT3_2") (pintype "passive"))
      (node (ref "U1") (pin "26") (pinfunction "IO26_26") (pintype "bidirectional"))
    )
    (net (code "30") (name "/StatusLED") (class "Default")
      (node (ref "R1") (pin "1") (pinfunction "1_1") (pintype "passive"))
      (node (ref "U1") (pin "5") (pinfunction "IO1_5") (pintype "bidirectional"))
    )
    (net (code "31") (name "/TWAI_RX") (class "Default")
      (node (ref "U1") (pin "32") (pinfunction "IO36_32") (pintype "bidirectional"))
      (node (ref "U5") (pin "4") (pinfunction "RXD_4") (pintype "passive"))
    )
    (net (code "32") (name "/TWAI_TX") (class "Default")
      (node (ref "U1") (pin "33") (pinfunction "IO37_33") (pintype "bidirectional"))
      (node (ref "U5") (pin "1") (pinfunction "TXD_1") (pintype "passive"))
    )
    (net (code "33") (name "/USB_D_N") (class "Default")
      (node (ref "J101") (pin "2") (pinfunction "D-_2") (pintype "passive"))
      (node (ref "U1") (pin "23") (pinfunction "IO19_23") (pintype "bidirectional"))
    )
    (net (code "34") (name "/USB_D_P") (class "Default")
      (node (ref "J101") (pin "3") (pinfunction "D+_3") (pintype "passive"))
      (node (ref "U1") (pin "24") (pinfunction "IO20_24") (pintype "bidirectional"))
    )
    (net (code "35") (name "GND") (class "Default")
      (node (ref "C11") (pin "1") (pinfunction "1_1") (pintype "passive"))
      (node (ref "C12") (pin "1") (pinfunction "1_1") (pintype "passive"))
      (node (ref "C13") (pin "2") (pinfunction "2_2") (pintype "passive"))
      (node (ref "C14") (pin "2") (pinfunction "2_2") (pintype "passive"))
      (node (ref "C15") (pin "2") (pinfunction "2_2") (pintype "passive"))
      (node (ref "C16") (pin "1") (pinfunction "1_1") (pintype "passive"))
      (node (ref "C31") (pin "1") (pinfunction "1_1") (pintype "passive"))
      (node (ref "C32") (pin "1") (pinfunction "1_1") (pintype "passive"))
      (node (ref "C33") (pin "1") (pinfunction "1_1") (pintype "passive"))
      (node (ref "C34") (pin "1") (pinfunction "1_1") (pintype "passive"))
      (node (ref "C35") (pin "1") (pinfunction "C_1") (pintype "passive"))
      (node (ref "C36") (pin "1") (pinfunction "C_1") (pintype "passive"))
      (node (ref "CAN_RX") (pin "2") (pinfunction "K_2") (pintype "passive"))
      (node (ref "CAN_TX") (pin "2") (pinfunction "K_2") (pintype "passive"))
      (node (ref "J101") (pin "10") (pinfunction "SHLD5_10") (pintype "passive"))
      (node (ref "J101") (pin "11") (pinfunction "SHLD6_11") (pintype "passive"))
      (node (ref "J101") (pin "5") (pinfunction "GND_5") (pintype "passive"))
      (node (ref "J101") (pin "6") (pinfunction "SHLD1_6") (pintype "passive"))
      (node (ref "J101") (pin "7") (pinfunction "SHLD2_7") (pintype "passive"))
      (node (ref "J101") (pin "8") (pinfunction "SHLD3_8") (pintype "passive"))
      (node (ref "J101") (pin "9") (pinfunction "SHLD4_9") (pintype "passive"))
      (node (ref "J201") (pin "2") (pinfunction "2_2") (pintype "passive"))
      (node (ref "J203") (pin "2") (pinfunction "2_2") (pintype "passive"))
      (node (ref "J204") (pin "2") (pinfunction "2_2") (pintype "passive"))
      (node (ref "J205") (pin "2") (pinfunction "2_2") (pintype "passive"))
      (node (ref "J206") (pin "2") (pinfunction "2_2") (pintype "passive"))
      (node (ref "PWR") (pin "2") (pinfunction "K_2") (pintype "passive"))
      (node (ref "Q5") (pin "2") (pinfunction "E_2") (pintype "passive"))
      (node (ref "Q6") (pin "2") (pinfunction "E_2") (pintype "passive"))
      (node (ref "Q7") (pin "2") (pinfunction "E_2") (pintype "passive"))
      (node (ref "Q8") (pin "2") (pinfunction "E_2") (pintype "passive"))
      (node (ref "R35") (pin "2") (pinfunction "2_2") (pintype "passive"))
      (node (ref "R38") (pin "2") (pinfunction "2_2") (pintype "passive"))
      (node (ref "R41") (pin "2") (pinfunction "2_2") (pintype "passive"))
      (node (ref "R44") (pin "2") (pinfunction "2_2") (pintype "passive"))
      (node (ref "SD1") (pin "10") (pinfunction "GND2_10") (pintype "passive"))
      (node (ref "SD1") (pin "11") (pinfunction "GND3_11") (pintype "passive"))
      (node (ref "SD1") (pin "12") (pinfunction "GND4_12") (pintype "passive"))
      (node (ref "SD1") (pin "6") (pinfunction "VSS_6") (pintype "passive"))
      (node (ref "SD1") (pin "9") (pinfunction "GND1_9") (pintype "passive"))
      (node (ref "SD_RX") (pin "2") (pinfunction "K_2") (pintype "passive"))
      (node (ref "SD_TX") (pin "2") (pinfunction "K_2") (pintype "passive"))
      (node (ref "SW1") (pin "3") (pinfunction "3_3") (pintype "passive"))
      (node (ref "SW1") (pin "4") (pinfunction "4_4") (pintype "passive"))
      (node (ref "SW1") (pin "5") (pinfunction "GND_5") (pintype "power_in"))
      (node (ref "Status") (pin "2") (pinfunction "K_2") (pintype "passive"))
      (node (ref "U1") (pin "1") (pinfunction "GND_1") (pintype "power_in"))
      (node (ref "U1") (pin "2") (pinfunction "GND_2") (pintype "power_in"))
      (node (ref "U1") (pin "42") (pinfunction "GND_42") (pintype "power_in"))
      (node (ref "U1") (pin "43") (pinfunction "GND_43") (pintype "power_in"))
      (node (ref "U1") (pin "46") (pinfunction "GND_46") (pintype "power_in"))
      (node (ref "U1") (pin "47") (pinfunction "GND_47") (pintype "power_in"))
      (node (ref "U1") (pin "48") (pinfunction "GND_48") (pintype "power_in"))
      (node (ref "U1") (pin "49") (pinfunction "GND_49") (pintype "power_in"))
      (node (ref "U1") (pin "50") (pinfunction "GND_50") (pintype "power_in"))
      (node (ref "U1") (pin "51") (pinfunction "GND_51") (pintype "power_in"))
      (node (ref "U1") (pin "52") (pinfunction "GND_52") (pintype "power_in"))
      (node (ref "U1") (pin "53") (pinfunction "GND_53") (pintype "power_in"))
      (node (ref "U1") (pin "54") (pinfunction "GND_54") (pintype "power_in"))
      (node (ref "U1") (pin "55") (pinfunction "GND_55") (pintype "power_in"))
      (node (ref "U1") (pin "56") (pinfunction "GND_56") (pintype "power_in"))
      (node (ref "U1") (pin "57") (pinfunction "GND_57") (pintype "power_in"))
      (node (ref "U1") (pin "58") (pinfunction "GND_58") (pintype "power_in"))
      (node (ref "U1") (pin "59") (pinfunction "GND_59") (pintype "power_in"))
      (node (ref "U1") (pin "60") (pinfunction "GND_60") (pintype "power_in"))
      (node (ref "U1") (pin "61") (pinfunction "GND_61") (pintype "power_in"))
      (node (ref "U1") (pin "61_1") (pinfunction "GND_61_1") (pintype "power_in"))
      (node (ref "U1") (pin "61_2") (pinfunction "GND_61_2") (pintype "power_in"))
      (node (ref "U1") (pin "61_3") (pinfunction "GND_61_3") (pintype "power_in"))
      (node (ref "U1") (pin "61_4") (pinfunction "GND_61_4") (pintype "power_in"))
      (node (ref "U1") (pin "61_5") (pinfunction "GND_61_5") (pintype "power_in"))
      (node (ref "U1") (pin "61_6") (pinfunction "GND_61_6") (pintype "power_in"))
      (node (ref "U1") (pin "61_7") (pinfunction "GND_61_7") (pintype "power_in"))
      (node (ref "U1") (pin "61_8") (pinfunction "GND_61_8") (pintype "power_in"))
      (node (ref "U1") (pin "62") (pinfunction "GND_62") (pintype "power_in"))
      (node (ref "U1") (pin "63") (pinfunction "GND_63") (pintype "power_in"))
      (node (ref "U1") (pin "64") (pinfunction "GND_64") (pintype "power_in"))
      (node (ref "U1") (pin "65") (pinfunction "GND_65") (pintype "power_in"))
      (node (ref "U2") (pin "5") (pinfunction "SDO/SA0_5") (pintype "output"))
      (node (ref "U2") (pin "8") (pinfunction "GND_8") (pintype "power_in"))
      (node (ref "U2") (pin "9") (pinfunction "GND_9") (pintype "power_in"))
      (node (ref "U201") (pin "15") (pinfunction "PGND_15") (pintype "power_in"))
      (node (ref "U201") (pin "16") (pinfunction "PGND_16") (pintype "power_in"))
      (node (ref "U201") (pin "17") (pinfunction "EP_17") (pintype "power_in"))
      (node (ref "U201") (pin "5") (pinfunction "FB_5") (pintype "input"))
      (node (ref "U201") (pin "6") (pinfunction "AGND_6") (pintype "power_in"))
      (node (ref "U201") (pin "8") (pinfunction "DEF_8") (pintype "input"))
      (node (ref "U3") (pin "1") (pinfunction "SDO/SA0_1") (pintype "output"))
      (node (ref "U3") (pin "2") (pinfunction "SDx_2") (pintype "bidirectional"))
      (node (ref "U3") (pin "3") (pinfunction "SCx_3") (pintype "input"))
      (node (ref "U3") (pin "6") (pinfunction "GND_6") (pintype "power_in"))
      (node (ref "U3") (pin "7") (pinfunction "GND_7") (pintype "power_in"))
      (node (ref "U4") (pin "6") (pinfunction "GND_6") (pintype "power_in"))
      (node (ref "U4") (pin "8") (pinfunction "GND_8") (pintype "power_in"))
      (node (ref "U5") (pin "2") (pinfunction "GND_2") (pintype "passive"))
      (node (ref "U5") (pin "8") (pinfunction "STB_8") (pintype "passive"))
    )
    (net (code "36") (name "Net-(CAN_RX-A)") (class "Default")
      (node (ref "CAN_RX") (pin "1") (pinfunction "A_1") (pintype "passive"))
      (node (ref "R3") (pin "2") (pinfunction "2_2") (pintype "passive"))
    )
    (net (code "37") (name "Net-(CAN_TX-A)") (class "Default")
      (node (ref "CAN_TX") (pin "1") (pinfunction "A_1") (pintype "passive"))
      (node (ref "R2") (pin "2") (pinfunction "2_2") (pintype "passive"))
    )
    (net (code "38") (name "Net-(L201-Pad1)") (class "Default")
      (node (ref "L201") (pin "1") (pinfunction "1_1") (pintype "passive"))
      (node (ref "U201") (pin "1") (pinfunction "SW_1") (pintype "power_in"))
      (node (ref "U201") (pin "2") (pinfunction "SW_2") (pintype "power_in"))
      (node (ref "U201") (pin "3") (pinfunction "SW_3") (pintype "power_in"))
    )
    (net (code "39") (name "Net-(PWR-A)") (class "Default")
      (node (ref "PWR") (pin "1") (pinfunction "A_1") (pintype "passive"))
      (node (ref "R6") (pin "2") (pinfunction "2_2") (pintype "passive"))
    )
    (net (code "40") (name "Net-(Q1-D)") (class "Default")
      (node (ref "J203") (pin "1") (pinfunction "1_1") (pintype "passive"))
      (node (ref "Q1") (pin "3") (pinfunction "D_3") (pintype "passive"))
    )
    (net (code "41") (name "Net-(Q1-G)") (class "Default")
      (node (ref "Q1") (pin "1") (pinfunction "G_1") (pintype "passive"))
      (node (ref "Q5") (pin "3") (pinfunction "C_3") (pintype "passive"))
      (node (ref "R33") (pin "2") (pinfunction "2_2") (pintype "passive"))
    )
    (net (code "42") (name "Net-(Q2-D)") (class "Default")
      (node (ref "J204") (pin "1") (pinfunction "1_1") (pintype "passive"))
      (node (ref "Q2") (pin "3") (pinfunction "D_3") (pintype "passive"))
    )
    (net (code "43") (name "Net-(Q2-G)") (class "Default")
      (node (ref "Q2") (pin "1") (pinfunction "G_1") (pintype "passive"))
      (node (ref "Q6") (pin "3") (pinfunction "C_3") (pintype "passive"))
      (node (ref "R36") (pin "2") (pinfunction "2_2") (pintype "passive"))
    )
    (net (code "44") (name "Net-(Q3-D)") (class "Default")
      (node (ref "J205") (pin "1") (pinfunction "1_1") (pintype "passive"))
      (node (ref "Q3") (pin "3") (pinfunction "D_3") (pintype "passive"))
    )
    (net (code "45") (name "Net-(Q3-G)") (class "Default")
      (node (ref "Q3") (pin "1") (pinfunction "G_1") (pintype "passive"))
      (node (ref "Q7") (pin "3") (pinfunction "C_3") (pintype "passive"))
      (node (ref "R39") (pin "2") (pinfunction "2_2") (pintype "passive"))
    )
    (net (code "46") (name "Net-(Q4-D)") (class "Default")
      (node (ref "J206") (pin "1") (pinfunction "1_1") (pintype "passive"))
      (node (ref "Q4") (pin "3") (pinfunction "D_3") (pintype "passive"))
    )
    (net (code "47") (name "Net-(Q4-G)") (class "Default")
      (node (ref "Q4") (pin "1") (pinfunction "G_1") (pintype "passive"))
      (node (ref "Q8") (pin "3") (pinfunction "C_3") (pintype "passive"))
      (node (ref "R42") (pin "2") (pinfunction "2_2") (pintype "passive"))
    )
    (net (code "48") (name "Net-(Q5-B)") (class "Default")
      (node (ref "Q5") (pin "1") (pinfunction "B_1") (pintype "passive"))
      (node (ref "R34") (pin "2") (pinfunction "2_2") (pintype "passive"))
      (node (ref "R35") (pin "1") (pinfunction "1_1") (pintype "passive"))
    )
    (net (code "49") (name "Net-(Q6-B)") (class "Default")
      (node (ref "Q6") (pin "1") (pinfunction "B_1") (pintype "passive"))
      (node (ref "R37") (pin "2") (pinfunction "2_2") (pintype "passive"))
      (node (ref "R38") (pin "1") (pinfunction "1_1") (pintype "passive"))
    )
    (net (code "50") (name "Net-(Q7-B)") (class "Default")
      (node (ref "Q7") (pin "1") (pinfunction "B_1") (pintype "passive"))
      (node (ref "R40") (pin "2") (pinfunction "2_2") (pintype "passive"))
      (node (ref "R41") (pin "1") (pinfunction "1_1") (pintype "passive"))
    )
    (net (code "51") (name "Net-(Q8-B)") (class "Default")
      (node (ref "Q8") (pin "1") (pinfunction "B_1") (pintype "passive"))
      (node (ref "R43") (pin "2") (pinfunction "2_2") (pintype "passive"))
      (node (ref "R44") (pin "1") (pinfunction "1_1") (pintype "passive"))
    )
    (net (code "52") (name "Net-(R104-Pad2)") (class "Default")
      (node (ref "R104") (pin "2") (pinfunction "2_2") (pintype "passive"))
      (node (ref "SW1") (pin "1") (pinfunction "1_1") (pintype "passive"))
    )
    (net (code "53") (name "Net-(SD_RX-A)") (class "Default")
      (node (ref "R5") (pin "2") (pinfunction "2_2") (pintype "passive"))
      (node (ref "SD_RX") (pin "1") (pinfunction "A_1") (pintype "passive"))
    )
    (net (code "54") (name "Net-(SD_TX-A)") (class "Default")
      (node (ref "R4") (pin "2") (pinfunction "2_2") (pintype "passive"))
      (node (ref "SD_TX") (pin "1") (pinfunction "A_1") (pintype "passive"))
    )
    (net (code "55") (name "Net-(Status-A)") (class "Default")
      (node (ref "R1") (pin "2") (pinfunction "2_2") (pintype "passive"))
      (node (ref "Status") (pin "1") (pinfunction "A_1") (pintype "passive"))
    )
    (net (code "56") (name "Net-(U2-CS)") (class "Default")
      (node (ref "R100") (pin "2") (pinfunction "2_2") (pintype "passive"))
      (node (ref "U2") (pin "6") (pinfunction "CS_6") (pintype "input"))
    )
    (net (code "57") (name "Net-(U3-CS)") (class "Default")
      (node (ref "R101") (pin "2") (pinfunction "2_2") (pintype "passive"))
      (node (ref "U3") (pin "12") (pinfunction "CS_12") (pintype "input"))
    )
    (net (code "58") (name "Net-(U4-C1)") (class "Default")
      (node (ref "C13") (pin "1") (pinfunction "1_1") (pintype "passive"))
      (node (ref "U4") (pin "5") (pinfunction "C1_5") (pintype "passive"))
    )
    (net (code "59") (name "Net-(U201-PG)") (class "Default")
      (node (ref "R31") (pin "1") (pinfunction "1_1") (pintype "passive"))
      (node (ref "U201") (pin "4") (pinfunction "PG_4") (pintype "tri_state"))
    )
    (net (code "60") (name "Net-(U201-SS{slash}TR)") (class "Default")
      (node (ref "C32") (pin "2") (pinfunction "2_2") (pintype "passive"))
      (node (ref "U201") (pin "9") (pinfunction "SS/TR_9") (pintype "input"))
    )
    (net (code "61") (name "unconnected-(J101-ID-Pad4)") (class "Default")
      (node (ref "J101") (pin "4") (pinfunction "ID_4") (pintype "passive+no_connect"))
    )
    (net (code "62") (name "unconnected-(U1-IO3-Pad7)") (class "Default")
      (node (ref "U1") (pin "7") (pinfunction "IO3_7") (pintype "bidirectional+no_connect"))
    )
    (net (code "63") (name "unconnected-(U1-IO5-Pad9)") (class "Default")
      (node (ref "U1") (pin "9") (pinfunction "IO5_9") (pintype "bidirectional"))
    )
    (net (code "64") (name "unconnected-(U1-IO14-Pad18)") (class "Default")
      (node (ref "U1") (pin "18") (pinfunction "IO14_18") (pintype "bidirectional"))
    )
    (net (code "65") (name "unconnected-(U1-IO15-Pad19)") (class "Default")
      (node (ref "U1") (pin "19") (pinfunction "IO15_19") (pintype "bidirectional"))
    )
    (net (code "66") (name "unconnected-(U1-IO16-Pad20)") (class "Default")
      (node (ref "U1") (pin "20") (pinfunction "IO16_20") (pintype "bidirectional"))
    )
    (net (code "67") (name "unconnected-(U1-IO17-Pad21)") (class "Default")
      (node (ref "U1") (pin "21") (pinfunction "IO17_21") (pintype "bidirectional"))
    )
    (net (code "68") (name "unconnected-(U1-IO18-Pad22)") (class "Default")
      (node (ref "U1") (pin "22") (pinfunction "IO18_22") (pintype "bidirectional"))
    )
    (net (code "69") (name "unconnected-(U1-IO33-Pad28)") (class "Default")
      (node (ref "U1") (pin "28") (pinfunction "IO33_28") (pintype "bidirectional"))
    )
    (net (code "70") (name "unconnected-(U1-IO45-Pad41)") (class "Default")
      (node (ref "U1") (pin "41") (pinfunction "IO45_41") (pintype "bidirectional+no_connect"))
    )
    (net (code "71") (name "unconnected-(U1-RXD0-Pad40)") (class "Default")
      (node (ref "U1") (pin "40") (pinfunction "RXD0_40") (pintype "bidirectional"))
    )
    (net (code "72") (name "unconnected-(U1-TXD0-Pad39)") (class "Default")
      (node (ref "U1") (pin "39") (pinfunction "TXD0_39") (pintype "bidirectional"))
    )
    (net (code "73") (name "unconnected-(U2-Reserved-Pad3)") (class "Default")
      (node (ref "U2") (pin "3") (pinfunction "Reserved_3") (pintype "passive+no_connect"))
    )
    (net (code "74") (name "unconnected-(U3-INT2-Pad9)") (class "Default")
      (node (ref "U3") (pin "9") (pinfunction "INT2_9") (pintype "input+no_connect"))
    )
    (net (code "75") (name "unconnected-(U3-OCS_Aux-Pad10)") (class "Default")
      (node (ref "U3") (pin "10") (pinfunction "OCS_Aux_10") (pintype "passive+no_connect"))
    )
    (net (code "76") (name "unconnected-(U3-SDO_Aux-Pad11)") (class "Default")
      (node (ref "U3") (pin "11") (pinfunction "SDO_Aux_11") (pintype "output+no_connect"))
    )
    (net (code "77") (name "unconnected-(U4-INT{slash}DRDY-Pad7)") (class "Default")
      (node (ref "U4") (pin "7") (pinfunction "INT/DRDY_7") (pintype "output"))
    )
    (net (code "78") (name "unconnected-(U4-NC-Pad2)") (class "Default")
      (node (ref "U4") (pin "2") (pinfunction "NC_2") (pintype "passive+no_connect"))
    )
    (net (code "79") (name "unconnected-(U4-NC-Pad11)") (class "Default")
      (node (ref "U4") (pin "11") (pinfunction "NC_11") (pintype "passive+no_connect"))
    )
    (net (code "80") (name "unconnected-(U4-NC-Pad12)") (class "Default")
      (node (ref "U4") (pin "12") (pinfunction "NC_12") (pintype "passive+no_connect"))
    )
  )
)
